# CorruptCore.net
KiCad netlist of a schematic drawn in EAGLE
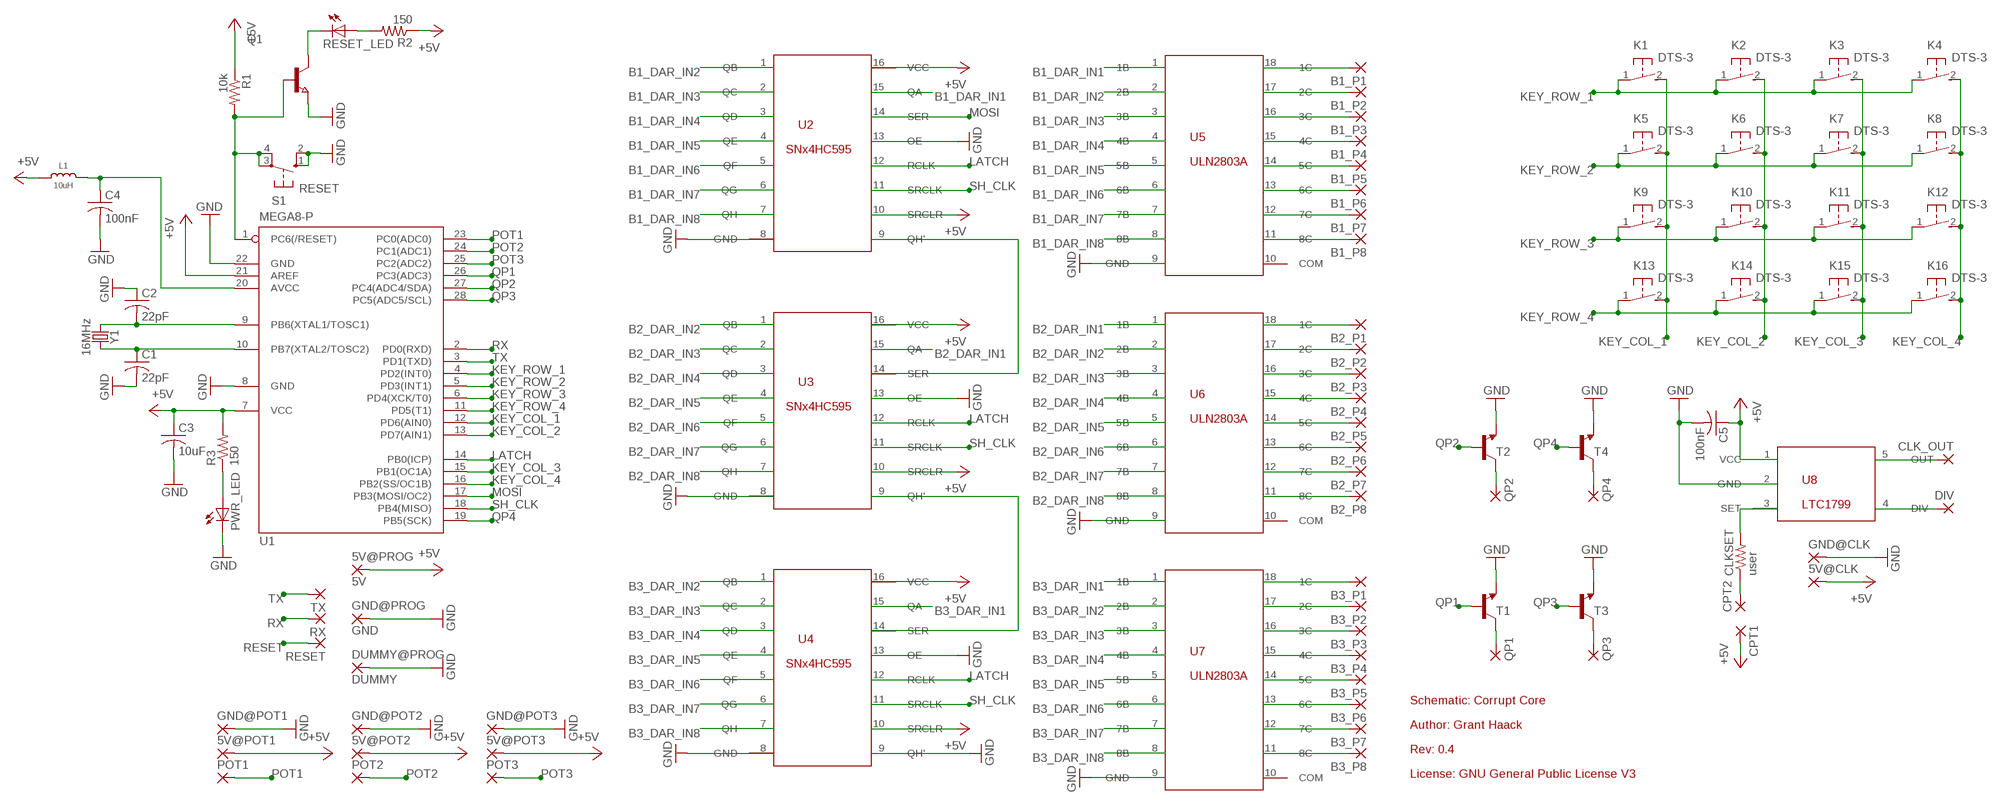
[diagram p0: schematic, sheet 1]

(export (version "E")
  (design (tool "Eeschema 10.0.6"))
  (components
    (comp (ref "5V@CLK")
      (value "1,6/0,8")
      (footprint "eagle-import:1,6_0,8")
      (libsource (lib "eagle-import") (part "1,6/0,8"))
    )
    (comp (ref "5V@POT1")
      (value "1,6/0,8")
      (footprint "eagle-import:1,6_0,8")
      (libsource (lib "eagle-import") (part "1,6/0,8"))
    )
    (comp (ref "5V@POT2")
      (value "1,6/0,8")
      (footprint "eagle-import:1,6_0,8")
      (libsource (lib "eagle-import") (part "1,6/0,8"))
    )
    (comp (ref "5V@POT3")
      (value "1,6/0,8")
      (footprint "eagle-import:1,6_0,8")
      (libsource (lib "eagle-import") (part "1,6/0,8"))
    )
    (comp (ref "5V@PROG")
      (value "5V")
      (footprint "eagle-import:1,6_0,8")
      (libsource (lib "eagle-import") (part "1,6/0,8"))
    )
    (comp (ref "B1_P1")
      (value "1,6/0,8")
      (footprint "eagle-import:1,6_0,8")
      (libsource (lib "eagle-import") (part "1,6/0,8"))
    )
    (comp (ref "B1_P2")
      (value "1,6/0,8")
      (footprint "eagle-import:1,6_0,8")
      (libsource (lib "eagle-import") (part "1,6/0,8"))
    )
    (comp (ref "B1_P3")
      (value "1,6/0,8")
      (footprint "eagle-import:1,6_0,8")
      (libsource (lib "eagle-import") (part "1,6/0,8"))
    )
    (comp (ref "B1_P4")
      (value "1,6/0,8")
      (footprint "eagle-import:1,6_0,8")
      (libsource (lib "eagle-import") (part "1,6/0,8"))
    )
    (comp (ref "B1_P5")
      (value "1,6/0,8")
      (footprint "eagle-import:1,6_0,8")
      (libsource (lib "eagle-import") (part "1,6/0,8"))
    )
    (comp (ref "B1_P6")
      (value "1,6/0,8")
      (footprint "eagle-import:1,6_0,8")
      (libsource (lib "eagle-import") (part "1,6/0,8"))
    )
    (comp (ref "B1_P7")
      (value "1,6/0,8")
      (footprint "eagle-import:1,6_0,8")
      (libsource (lib "eagle-import") (part "1,6/0,8"))
    )
    (comp (ref "B1_P8")
      (value "1,6/0,8")
      (footprint "eagle-import:1,6_0,8")
      (libsource (lib "eagle-import") (part "1,6/0,8"))
    )
    (comp (ref "B2_P1")
      (value "1,6/0,8")
      (footprint "eagle-import:1,6_0,8")
      (libsource (lib "eagle-import") (part "1,6/0,8"))
    )
    (comp (ref "B2_P2")
      (value "1,6/0,8")
      (footprint "eagle-import:1,6_0,8")
      (libsource (lib "eagle-import") (part "1,6/0,8"))
    )
    (comp (ref "B2_P3")
      (value "1,6/0,8")
      (footprint "eagle-import:1,6_0,8")
      (libsource (lib "eagle-import") (part "1,6/0,8"))
    )
    (comp (ref "B2_P4")
      (value "1,6/0,8")
      (footprint "eagle-import:1,6_0,8")
      (libsource (lib "eagle-import") (part "1,6/0,8"))
    )
    (comp (ref "B2_P5")
      (value "1,6/0,8")
      (footprint "eagle-import:1,6_0,8")
      (libsource (lib "eagle-import") (part "1,6/0,8"))
    )
    (comp (ref "B2_P6")
      (value "1,6/0,8")
      (footprint "eagle-import:1,6_0,8")
      (libsource (lib "eagle-import") (part "1,6/0,8"))
    )
    (comp (ref "B2_P7")
      (value "1,6/0,8")
      (footprint "eagle-import:1,6_0,8")
      (libsource (lib "eagle-import") (part "1,6/0,8"))
    )
    (comp (ref "B2_P8")
      (value "1,6/0,8")
      (footprint "eagle-import:1,6_0,8")
      (libsource (lib "eagle-import") (part "1,6/0,8"))
    )
    (comp (ref "B3_P1")
      (value "1,6/0,8")
      (footprint "eagle-import:1,6_0,8")
      (libsource (lib "eagle-import") (part "1,6/0,8"))
    )
    (comp (ref "B3_P2")
      (value "1,6/0,8")
      (footprint "eagle-import:1,6_0,8")
      (libsource (lib "eagle-import") (part "1,6/0,8"))
    )
    (comp (ref "B3_P3")
      (value "1,6/0,8")
      (footprint "eagle-import:1,6_0,8")
      (libsource (lib "eagle-import") (part "1,6/0,8"))
    )
    (comp (ref "B3_P4")
      (value "1,6/0,8")
      (footprint "eagle-import:1,6_0,8")
      (libsource (lib "eagle-import") (part "1,6/0,8"))
    )
    (comp (ref "B3_P5")
      (value "1,6/0,8")
      (footprint "eagle-import:1,6_0,8")
      (libsource (lib "eagle-import") (part "1,6/0,8"))
    )
    (comp (ref "B3_P6")
      (value "1,6/0,8")
      (footprint "eagle-import:1,6_0,8")
      (libsource (lib "eagle-import") (part "1,6/0,8"))
    )
    (comp (ref "B3_P7")
      (value "1,6/0,8")
      (footprint "eagle-import:1,6_0,8")
      (libsource (lib "eagle-import") (part "1,6/0,8"))
    )
    (comp (ref "B3_P8")
      (value "1,6/0,8")
      (footprint "eagle-import:1,6_0,8")
      (libsource (lib "eagle-import") (part "1,6/0,8"))
    )
    (comp (ref "C1")
      (value "22pF")
      (footprint "eagle-import:C0805")
      (libsource (lib "eagle-import") (part "C-USC0805"))
    )
    (comp (ref "C2")
      (value "22pF")
      (footprint "eagle-import:C0805")
      (libsource (lib "eagle-import") (part "C-USC0805"))
    )
    (comp (ref "C3")
      (value "10uF")
      (footprint "eagle-import:C0805")
      (libsource (lib "eagle-import") (part "C-USC0805"))
    )
    (comp (ref "C4")
      (value "100nF")
      (footprint "eagle-import:C0805")
      (libsource (lib "eagle-import") (part "C-USC0805"))
    )
    (comp (ref "C5")
      (value "100nF")
      (footprint "eagle-import:C0805")
      (libsource (lib "eagle-import") (part "C-USC0805"))
    )
    (comp (ref "CLKSET")
      (value "user")
      (footprint "eagle-import:0207_7")
      (libsource (lib "eagle-import") (part "R-US_0207/7"))
    )
    (comp (ref "CLK_OUT")
      (value "1,6/0,8")
      (footprint "eagle-import:1,6_0,8")
      (libsource (lib "eagle-import") (part "1,6/0,8"))
    )
    (comp (ref "CPT1")
      (value "1,6/0,8")
      (footprint "eagle-import:1,6_0,8")
      (libsource (lib "eagle-import") (part "1,6/0,8"))
    )
    (comp (ref "CPT2")
      (value "1,6/0,8")
      (footprint "eagle-import:1,6_0,8")
      (libsource (lib "eagle-import") (part "1,6/0,8"))
    )
    (comp (ref "DIV")
      (value "1,6/0,8")
      (footprint "eagle-import:1,6_0,8")
      (libsource (lib "eagle-import") (part "1,6/0,8"))
    )
    (comp (ref "DUMMY@PROG")
      (value "DUMMY")
      (footprint "eagle-import:1,6_0,8")
      (libsource (lib "eagle-import") (part "1,6/0,8"))
    )
    (comp (ref "GND@CLK")
      (value "1,6/0,8")
      (footprint "eagle-import:1,6_0,8")
      (libsource (lib "eagle-import") (part "1,6/0,8"))
    )
    (comp (ref "GND@POT1")
      (value "1,6/0,8")
      (footprint "eagle-import:1,6_0,8")
      (libsource (lib "eagle-import") (part "1,6/0,8"))
    )
    (comp (ref "GND@POT2")
      (value "1,6/0,8")
      (footprint "eagle-import:1,6_0,8")
      (libsource (lib "eagle-import") (part "1,6/0,8"))
    )
    (comp (ref "GND@POT3")
      (value "1,6/0,8")
      (footprint "eagle-import:1,6_0,8")
      (libsource (lib "eagle-import") (part "1,6/0,8"))
    )
    (comp (ref "GND@PROG")
      (value "GND")
      (footprint "eagle-import:1,6_0,8")
      (libsource (lib "eagle-import") (part "1,6/0,8"))
    )
    (comp (ref "K1")
      (value "DTS-3")
      (footprint "eagle-import:DTS-3")
      (libsource (lib "eagle-import") (part "DTS-3"))
    )
    (comp (ref "K2")
      (value "DTS-3")
      (footprint "eagle-import:DTS-3")
      (libsource (lib "eagle-import") (part "DTS-3"))
    )
    (comp (ref "K3")
      (value "DTS-3")
      (footprint "eagle-import:DTS-3")
      (libsource (lib "eagle-import") (part "DTS-3"))
    )
    (comp (ref "K4")
      (value "DTS-3")
      (footprint "eagle-import:DTS-3")
      (libsource (lib "eagle-import") (part "DTS-3"))
    )
    (comp (ref "K5")
      (value "DTS-3")
      (footprint "eagle-import:DTS-3")
      (libsource (lib "eagle-import") (part "DTS-3"))
    )
    (comp (ref "K6")
      (value "DTS-3")
      (footprint "eagle-import:DTS-3")
      (libsource (lib "eagle-import") (part "DTS-3"))
    )
    (comp (ref "K7")
      (value "DTS-3")
      (footprint "eagle-import:DTS-3")
      (libsource (lib "eagle-import") (part "DTS-3"))
    )
    (comp (ref "K8")
      (value "DTS-3")
      (footprint "eagle-import:DTS-3")
      (libsource (lib "eagle-import") (part "DTS-3"))
    )
    (comp (ref "K9")
      (value "DTS-3")
      (footprint "eagle-import:DTS-3")
      (libsource (lib "eagle-import") (part "DTS-3"))
    )
    (comp (ref "K10")
      (value "DTS-3")
      (footprint "eagle-import:DTS-3")
      (libsource (lib "eagle-import") (part "DTS-3"))
    )
    (comp (ref "K11")
      (value "DTS-3")
      (footprint "eagle-import:DTS-3")
      (libsource (lib "eagle-import") (part "DTS-3"))
    )
    (comp (ref "K12")
      (value "DTS-3")
      (footprint "eagle-import:DTS-3")
      (libsource (lib "eagle-import") (part "DTS-3"))
    )
    (comp (ref "K13")
      (value "DTS-3")
      (footprint "eagle-import:DTS-3")
      (libsource (lib "eagle-import") (part "DTS-3"))
    )
    (comp (ref "K14")
      (value "DTS-3")
      (footprint "eagle-import:DTS-3")
      (libsource (lib "eagle-import") (part "DTS-3"))
    )
    (comp (ref "K15")
      (value "DTS-3")
      (footprint "eagle-import:DTS-3")
      (libsource (lib "eagle-import") (part "DTS-3"))
    )
    (comp (ref "K16")
      (value "DTS-3")
      (footprint "eagle-import:DTS-3")
      (libsource (lib "eagle-import") (part "DTS-3"))
    )
    (comp (ref "L1")
      (value "10uH")
      (footprint "eagle-import:MICROBUILDER__0805")
      (libsource (lib "eagle-import") (part "MICROBUILDER_INDUCTOR_0805"))
    )
    (comp (ref "POT1")
      (value "1,6/0,8")
      (footprint "eagle-import:1,6_0,8")
      (libsource (lib "eagle-import") (part "1,6/0,8"))
    )
    (comp (ref "POT2")
      (value "1,6/0,8")
      (footprint "eagle-import:1,6_0,8")
      (libsource (lib "eagle-import") (part "1,6/0,8"))
    )
    (comp (ref "POT3")
      (value "1,6/0,8")
      (footprint "eagle-import:1,6_0,8")
      (libsource (lib "eagle-import") (part "1,6/0,8"))
    )
    (comp (ref "PWR_LED")
      (value "LEDCHIPLED_0603")
      (footprint "eagle-import:CHIPLED_0603")
      (libsource (lib "eagle-import") (part "LEDCHIPLED_0603"))
    )
    (comp (ref "Q1")
      (value "NPN-TRANSISTOR_SOT23")
      (footprint "eagle-import:SOT23")
      (libsource (lib "eagle-import") (part "NPN-TRANSISTOR_SOT23"))
    )
    (comp (ref "QP1")
      (value "1,6/0,8")
      (footprint "eagle-import:1,6_0,8")
      (libsource (lib "eagle-import") (part "1,6/0,8"))
    )
    (comp (ref "QP2")
      (value "1,6/0,8")
      (footprint "eagle-import:1,6_0,8")
      (libsource (lib "eagle-import") (part "1,6/0,8"))
    )
    (comp (ref "QP3")
      (value "1,6/0,8")
      (footprint "eagle-import:1,6_0,8")
      (libsource (lib "eagle-import") (part "1,6/0,8"))
    )
    (comp (ref "QP4")
      (value "1,6/0,8")
      (footprint "eagle-import:1,6_0,8")
      (libsource (lib "eagle-import") (part "1,6/0,8"))
    )
    (comp (ref "R1")
      (value "10k")
      (footprint "eagle-import:R0805")
      (libsource (lib "eagle-import") (part "R-US_R0805"))
    )
    (comp (ref "R2")
      (value "150")
      (footprint "eagle-import:R0805")
      (libsource (lib "eagle-import") (part "R-US_R0805"))
    )
    (comp (ref "R3")
      (value "150")
      (footprint "eagle-import:R0805")
      (libsource (lib "eagle-import") (part "R-US_R0805"))
    )
    (comp (ref "RESET")
      (value "1,6/0,8")
      (footprint "eagle-import:1,6_0,8")
      (libsource (lib "eagle-import") (part "1,6/0,8"))
    )
    (comp (ref "RESET_LED")
      (value "LEDCHIPLED_0603")
      (footprint "eagle-import:CHIPLED_0603")
      (libsource (lib "eagle-import") (part "LEDCHIPLED_0603"))
    )
    (comp (ref "RX")
      (value "1,6/0,8")
      (footprint "eagle-import:1,6_0,8")
      (libsource (lib "eagle-import") (part "1,6/0,8"))
    )
    (comp (ref "S1")
      (value "RESET")
      (footprint "eagle-import:B3F-10XX")
      (fields (field (name "MPN") "B3F-1000"))
      (libsource (lib "eagle-import") (part "10-XX"))
    )
    (comp (ref "T1")
      (value "TRANS_NPN-MMBTA42")
      (footprint "eagle-import:SOT23-3")
      (libsource (lib "eagle-import") (part "TRANS_NPN-MMBTA42"))
    )
    (comp (ref "T2")
      (value "TRANS_NPN-MMBTA42")
      (footprint "eagle-import:SOT23-3")
      (libsource (lib "eagle-import") (part "TRANS_NPN-MMBTA42"))
    )
    (comp (ref "T3")
      (value "TRANS_NPN-MMBTA42")
      (footprint "eagle-import:SOT23-3")
      (libsource (lib "eagle-import") (part "TRANS_NPN-MMBTA42"))
    )
    (comp (ref "T4")
      (value "TRANS_NPN-MMBTA42")
      (footprint "eagle-import:SOT23-3")
      (libsource (lib "eagle-import") (part "TRANS_NPN-MMBTA42"))
    )
    (comp (ref "TX")
      (value "1,6/0,8")
      (footprint "eagle-import:1,6_0,8")
      (libsource (lib "eagle-import") (part "1,6/0,8"))
    )
    (comp (ref "U1")
      (value "MEGA8-P")
      (footprint "eagle-import:DIL28-3")
      (libsource (lib "eagle-import") (part "MEGA8-P"))
    )
    (comp (ref "U2")
      (value "SNX4HC595SOIC16")
      (footprint "eagle-import:SOIC16N")
      (libsource (lib "eagle-import") (part "SNX4HC595SOIC16"))
    )
    (comp (ref "U3")
      (value "SNX4HC595SOIC16")
      (footprint "eagle-import:SOIC16N")
      (libsource (lib "eagle-import") (part "SNX4HC595SOIC16"))
    )
    (comp (ref "U4")
      (value "SNX4HC595SOIC16")
      (footprint "eagle-import:SOIC16N")
      (libsource (lib "eagle-import") (part "SNX4HC595SOIC16"))
    )
    (comp (ref "U5")
      (value "ULN2803ASOIC18")
      (footprint "eagle-import:SO18L")
      (libsource (lib "eagle-import") (part "ULN2803ASOIC18"))
    )
    (comp (ref "U6")
      (value "ULN2803ASOIC18")
      (footprint "eagle-import:SO18L")
      (libsource (lib "eagle-import") (part "ULN2803ASOIC18"))
    )
    (comp (ref "U7")
      (value "ULN2803ASOIC18")
      (footprint "eagle-import:SO18L")
      (libsource (lib "eagle-import") (part "ULN2803ASOIC18"))
    )
    (comp (ref "U8")
      (value "LTC1799")
      (footprint "eagle-import:SOT23-5L")
      (libsource (lib "eagle-import") (part "LTC1799"))
    )
    (comp (ref "Y1")
      (value "16MHz")
      (footprint "eagle-import:HC49US")
      (libsource (lib "eagle-import") (part "CRYSTAL-16MHZPTH-HC49US"))
    )
  )
  (nets
    (net (code "1") (name "+5V") (class "Default")
      (node (ref "5V@CLK") (pin "1") (pinfunction "P_1") (pintype "passive"))
      (node (ref "5V@POT1") (pin "1") (pinfunction "P_1") (pintype "passive"))
      (node (ref "5V@POT2") (pin "1") (pinfunction "P_1") (pintype "passive"))
      (node (ref "5V@POT3") (pin "1") (pinfunction "P_1") (pintype "passive"))
      (node (ref "5V@PROG") (pin "1") (pinfunction "P_1") (pintype "passive"))
      (node (ref "C3") (pin "1") (pinfunction "1_1") (pintype "passive"))
      (node (ref "C5") (pin "1") (pinfunction "1_1") (pintype "passive"))
      (node (ref "CPT1") (pin "1") (pinfunction "P_1") (pintype "passive"))
      (node (ref "L1") (pin "1") (pinfunction "1_1") (pintype "passive"))
      (node (ref "R1") (pin "1") (pinfunction "1_1") (pintype "passive"))
      (node (ref "R2") (pin "1") (pinfunction "1_1") (pintype "passive"))
      (node (ref "R3") (pin "2") (pinfunction "2_2") (pintype "passive"))
      (node (ref "U1") (pin "21") (pinfunction "AREF_21") (pintype "passive"))
      (node (ref "U1") (pin "7") (pinfunction "VCC_7") (pintype "power_in"))
      (node (ref "U2") (pin "10") (pinfunction "SRCLR_10") (pintype "bidirectional"))
      (node (ref "U2") (pin "16") (pinfunction "VCC_16") (pintype "bidirectional"))
      (node (ref "U3") (pin "10") (pinfunction "SRCLR_10") (pintype "bidirectional"))
      (node (ref "U3") (pin "16") (pinfunction "VCC_16") (pintype "bidirectional"))
      (node (ref "U4") (pin "10") (pinfunction "SRCLR_10") (pintype "bidirectional"))
      (node (ref "U4") (pin "16") (pinfunction "VCC_16") (pintype "bidirectional"))
      (node (ref "U8") (pin "1") (pinfunction "VCC_1") (pintype "bidirectional"))
    )
    (net (code "2") (name "/B1_DAR_IN1") (class "Default")
      (node (ref "U2") (pin "15") (pinfunction "QA_15") (pintype "bidirectional"))
      (node (ref "U5") (pin "1") (pinfunction "1B_1") (pintype "bidirectional"))
    )
    (net (code "3") (name "/B1_DAR_IN2") (class "Default")
      (node (ref "U2") (pin "1") (pinfunction "QB_1") (pintype "bidirectional"))
      (node (ref "U5") (pin "2") (pinfunction "2B_2") (pintype "bidirectional"))
    )
    (net (code "4") (name "/B1_DAR_IN3") (class "Default")
      (node (ref "U2") (pin "2") (pinfunction "QC_2") (pintype "bidirectional"))
      (node (ref "U5") (pin "3") (pinfunction "3B_3") (pintype "bidirectional"))
    )
    (net (code "5") (name "/B1_DAR_IN4") (class "Default")
      (node (ref "U2") (pin "3") (pinfunction "QD_3") (pintype "bidirectional"))
      (node (ref "U5") (pin "4") (pinfunction "4B_4") (pintype "bidirectional"))
    )
    (net (code "6") (name "/B1_DAR_IN5") (class "Default")
      (node (ref "U2") (pin "4") (pinfunction "QE_4") (pintype "bidirectional"))
      (node (ref "U5") (pin "5") (pinfunction "5B_5") (pintype "bidirectional"))
    )
    (net (code "7") (name "/B1_DAR_IN6") (class "Default")
      (node (ref "U2") (pin "5") (pinfunction "QF_5") (pintype "bidirectional"))
      (node (ref "U5") (pin "6") (pinfunction "6B_6") (pintype "bidirectional"))
    )
    (net (code "8") (name "/B1_DAR_IN7") (class "Default")
      (node (ref "U2") (pin "6") (pinfunction "QG_6") (pintype "bidirectional"))
      (node (ref "U5") (pin "7") (pinfunction "7B_7") (pintype "bidirectional"))
    )
    (net (code "9") (name "/B1_DAR_IN8") (class "Default")
      (node (ref "U2") (pin "7") (pinfunction "QH_7") (pintype "bidirectional"))
      (node (ref "U5") (pin "8") (pinfunction "8B_8") (pintype "bidirectional"))
    )
    (net (code "10") (name "/B2_DAR_IN1") (class "Default")
      (node (ref "U3") (pin "15") (pinfunction "QA_15") (pintype "bidirectional"))
      (node (ref "U6") (pin "1") (pinfunction "1B_1") (pintype "bidirectional"))
    )
    (net (code "11") (name "/B2_DAR_IN2") (class "Default")
      (node (ref "U3") (pin "1") (pinfunction "QB_1") (pintype "bidirectional"))
      (node (ref "U6") (pin "2") (pinfunction "2B_2") (pintype "bidirectional"))
    )
    (net (code "12") (name "/B2_DAR_IN3") (class "Default")
      (node (ref "U3") (pin "2") (pinfunction "QC_2") (pintype "bidirectional"))
      (node (ref "U6") (pin "3") (pinfunction "3B_3") (pintype "bidirectional"))
    )
    (net (code "13") (name "/B2_DAR_IN4") (class "Default")
      (node (ref "U3") (pin "3") (pinfunction "QD_3") (pintype "bidirectional"))
      (node (ref "U6") (pin "4") (pinfunction "4B_4") (pintype "bidirectional"))
    )
    (net (code "14") (name "/B2_DAR_IN5") (class "Default")
      (node (ref "U3") (pin "4") (pinfunction "QE_4") (pintype "bidirectional"))
      (node (ref "U6") (pin "5") (pinfunction "5B_5") (pintype "bidirectional"))
    )
    (net (code "15") (name "/B2_DAR_IN6") (class "Default")
      (node (ref "U3") (pin "5") (pinfunction "QF_5") (pintype "bidirectional"))
      (node (ref "U6") (pin "6") (pinfunction "6B_6") (pintype "bidirectional"))
    )
    (net (code "16") (name "/B2_DAR_IN7") (class "Default")
      (node (ref "U3") (pin "6") (pinfunction "QG_6") (pintype "bidirectional"))
      (node (ref "U6") (pin "7") (pinfunction "7B_7") (pintype "bidirectional"))
    )
    (net (code "17") (name "/B2_DAR_IN8") (class "Default")
      (node (ref "U3") (pin "7") (pinfunction "QH_7") (pintype "bidirectional"))
      (node (ref "U6") (pin "8") (pinfunction "8B_8") (pintype "bidirectional"))
    )
    (net (code "18") (name "/B3_DAR_IN1") (class "Default")
      (node (ref "U4") (pin "15") (pinfunction "QA_15") (pintype "bidirectional"))
      (node (ref "U7") (pin "1") (pinfunction "1B_1") (pintype "bidirectional"))
    )
    (net (code "19") (name "/B3_DAR_IN2") (class "Default")
      (node (ref "U4") (pin "1") (pinfunction "QB_1") (pintype "bidirectional"))
      (node (ref "U7") (pin "2") (pinfunction "2B_2") (pintype "bidirectional"))
    )
    (net (code "20") (name "/B3_DAR_IN3") (class "Default")
      (node (ref "U4") (pin "2") (pinfunction "QC_2") (pintype "bidirectional"))
      (node (ref "U7") (pin "3") (pinfunction "3B_3") (pintype "bidirectional"))
    )
    (net (code "21") (name "/B3_DAR_IN4") (class "Default")
      (node (ref "U4") (pin "3") (pinfunction "QD_3") (pintype "bidirectional"))
      (node (ref "U7") (pin "4") (pinfunction "4B_4") (pintype "bidirectional"))
    )
    (net (code "22") (name "/B3_DAR_IN5") (class "Default")
      (node (ref "U4") (pin "4") (pinfunction "QE_4") (pintype "bidirectional"))
      (node (ref "U7") (pin "5") (pinfunction "5B_5") (pintype "bidirectional"))
    )
    (net (code "23") (name "/B3_DAR_IN6") (class "Default")
      (node (ref "U4") (pin "5") (pinfunction "QF_5") (pintype "bidirectional"))
      (node (ref "U7") (pin "6") (pinfunction "6B_6") (pintype "bidirectional"))
    )
    (net (code "24") (name "/B3_DAR_IN7") (class "Default")
      (node (ref "U4") (pin "6") (pinfunction "QG_6") (pintype "bidirectional"))
      (node (ref "U7") (pin "7") (pinfunction "7B_7") (pintype "bidirectional"))
    )
    (net (code "25") (name "/B3_DAR_IN8") (class "Default")
      (node (ref "U4") (pin "7") (pinfunction "QH_7") (pintype "bidirectional"))
      (node (ref "U7") (pin "8") (pinfunction "8B_8") (pintype "bidirectional"))
    )
    (net (code "26") (name "/KEY_COL_1") (class "Default")
      (node (ref "K1") (pin "2") (pinfunction "2_2") (pintype "passive"))
      (node (ref "K13") (pin "2") (pinfunction "2_2") (pintype "passive"))
      (node (ref "K5") (pin "2") (pinfunction "2_2") (pintype "passive"))
      (node (ref "K9") (pin "2") (pinfunction "2_2") (pintype "passive"))
      (node (ref "U1") (pin "12") (pinfunction "PD6(AIN0)_12") (pintype "bidirectional"))
    )
    (net (code "27") (name "/KEY_COL_2") (class "Default")
      (node (ref "K10") (pin "2") (pinfunction "2_2") (pintype "passive"))
      (node (ref "K14") (pin "2") (pinfunction "2_2") (pintype "passive"))
      (node (ref "K2") (pin "2") (pinfunction "2_2") (pintype "passive"))
      (node (ref "K6") (pin "2") (pinfunction "2_2") (pintype "passive"))
      (node (ref "U1") (pin "13") (pinfunction "PD7(AIN1)_13") (pintype "bidirectional"))
    )
    (net (code "28") (name "/KEY_COL_3") (class "Default")
      (node (ref "K11") (pin "2") (pinfunction "2_2") (pintype "passive"))
      (node (ref "K15") (pin "2") (pinfunction "2_2") (pintype "passive"))
      (node (ref "K3") (pin "2") (pinfunction "2_2") (pintype "passive"))
      (node (ref "K7") (pin "2") (pinfunction "2_2") (pintype "passive"))
      (node (ref "U1") (pin "15") (pinfunction "PB1(OC1A)_15") (pintype "bidirectional"))
    )
    (net (code "29") (name "/KEY_COL_4") (class "Default")
      (node (ref "K12") (pin "2") (pinfunction "2_2") (pintype "passive"))
      (node (ref "K16") (pin "2") (pinfunction "2_2") (pintype "passive"))
      (node (ref "K4") (pin "2") (pinfunction "2_2") (pintype "passive"))
      (node (ref "K8") (pin "2") (pinfunction "2_2") (pintype "passive"))
      (node (ref "U1") (pin "16") (pinfunction "PB2(SS/OC1B)_16") (pintype "bidirectional"))
    )
    (net (code "30") (name "/KEY_ROW_1") (class "Default")
      (node (ref "K1") (pin "1") (pinfunction "1_1") (pintype "passive"))
      (node (ref "K2") (pin "1") (pinfunction "1_1") (pintype "passive"))
      (node (ref "K3") (pin "1") (pinfunction "1_1") (pintype "passive"))
      (node (ref "K4") (pin "1") (pinfunction "1_1") (pintype "passive"))
      (node (ref "U1") (pin "4") (pinfunction "PD2(INT0)_4") (pintype "bidirectional"))
    )
    (net (code "31") (name "/KEY_ROW_2") (class "Default")
      (node (ref "K5") (pin "1") (pinfunction "1_1") (pintype "passive"))
      (node (ref "K6") (pin "1") (pinfunction "1_1") (pintype "passive"))
      (node (ref "K7") (pin "1") (pinfunction "1_1") (pintype "passive"))
      (node (ref "K8") (pin "1") (pinfunction "1_1") (pintype "passive"))
      (node (ref "U1") (pin "5") (pinfunction "PD3(INT1)_5") (pintype "bidirectional"))
    )
    (net (code "32") (name "/KEY_ROW_3") (class "Default")
      (node (ref "K10") (pin "1") (pinfunction "1_1") (pintype "passive"))
      (node (ref "K11") (pin "1") (pinfunction "1_1") (pintype "passive"))
      (node (ref "K12") (pin "1") (pinfunction "1_1") (pintype "passive"))
      (node (ref "K9") (pin "1") (pinfunction "1_1") (pintype "passive"))
      (node (ref "U1") (pin "6") (pinfunction "PD4(XCK/T0)_6") (pintype "bidirectional"))
    )
    (net (code "33") (name "/KEY_ROW_4") (class "Default")
      (node (ref "K13") (pin "1") (pinfunction "1_1") (pintype "passive"))
      (node (ref "K14") (pin "1") (pinfunction "1_1") (pintype "passive"))
      (node (ref "K15") (pin "1") (pinfunction "1_1") (pintype "passive"))
      (node (ref "K16") (pin "1") (pinfunction "1_1") (pintype "passive"))
      (node (ref "U1") (pin "11") (pinfunction "PD5(T1)_11") (pintype "bidirectional"))
    )
    (net (code "34") (name "/LATCH") (class "Default")
      (node (ref "U1") (pin "14") (pinfunction "PB0(ICP)_14") (pintype "bidirectional"))
      (node (ref "U2") (pin "12") (pinfunction "RCLK_12") (pintype "bidirectional"))
      (node (ref "U3") (pin "12") (pinfunction "RCLK_12") (pintype "bidirectional"))
      (node (ref "U4") (pin "12") (pinfunction "RCLK_12") (pintype "bidirectional"))
    )
    (net (code "35") (name "/MOSI") (class "Default")
      (node (ref "U1") (pin "17") (pinfunction "PB3(MOSI/OC2)_17") (pintype "bidirectional"))
      (node (ref "U2") (pin "14") (pinfunction "SER_14") (pintype "bidirectional"))
    )
    (net (code "36") (name "/POT1") (class "Default")
      (node (ref "POT1") (pin "1") (pinfunction "P_1") (pintype "passive"))
      (node (ref "U1") (pin "23") (pinfunction "PC0(ADC0)_23") (pintype "bidirectional"))
    )
    (net (code "37") (name "/POT2") (class "Default")
      (node (ref "POT2") (pin "1") (pinfunction "P_1") (pintype "passive"))
      (node (ref "U1") (pin "24") (pinfunction "PC1(ADC1)_24") (pintype "bidirectional"))
    )
    (net (code "38") (name "/POT3") (class "Default")
      (node (ref "POT3") (pin "1") (pinfunction "P_1") (pintype "passive"))
      (node (ref "U1") (pin "25") (pinfunction "PC2(ADC2)_25") (pintype "bidirectional"))
    )
    (net (code "39") (name "/QP1") (class "Default")
      (node (ref "T1") (pin "1") (pinfunction "B_1") (pintype "passive"))
      (node (ref "U1") (pin "26") (pinfunction "PC3(ADC3)_26") (pintype "bidirectional"))
    )
    (net (code "40") (name "/QP2") (class "Default")
      (node (ref "T2") (pin "1") (pinfunction "B_1") (pintype "passive"))
      (node (ref "U1") (pin "27") (pinfunction "PC4(ADC4/SDA)_27") (pintype "bidirectional"))
    )
    (net (code "41") (name "/QP3") (class "Default")
      (node (ref "T3") (pin "1") (pinfunction "B_1") (pintype "passive"))
      (node (ref "U1") (pin "28") (pinfunction "PC5(ADC5/SCL)_28") (pintype "bidirectional"))
    )
    (net (code "42") (name "/QP4") (class "Default")
      (node (ref "T4") (pin "1") (pinfunction "B_1") (pintype "passive"))
      (node (ref "U1") (pin "19") (pinfunction "PB5(SCK)_19") (pintype "bidirectional"))
    )
    (net (code "43") (name "/RESET") (class "Default")
      (node (ref "Q1") (pin "1") (pinfunction "B_1") (pintype "passive"))
      (node (ref "R1") (pin "2") (pinfunction "2_2") (pintype "passive"))
      (node (ref "RESET") (pin "1") (pinfunction "P_1") (pintype "passive"))
      (node (ref "S1") (pin "3") (pinfunction "P_3") (pintype "passive"))
      (node (ref "S1") (pin "4") (pinfunction "P1_4") (pintype "passive"))
      (node (ref "U1") (pin "1") (pinfunction "PC6(/RESET)_1") (pintype "bidirectional"))
    )
    (net (code "44") (name "/RX") (class "Default")
      (node (ref "RX") (pin "1") (pinfunction "P_1") (pintype "passive"))
      (node (ref "U1") (pin "2") (pinfunction "PD0(RXD)_2") (pintype "bidirectional"))
    )
    (net (code "45") (name "/SH_CLK") (class "Default")
      (node (ref "U1") (pin "18") (pinfunction "PB4(MISO)_18") (pintype "bidirectional"))
      (node (ref "U2") (pin "11") (pinfunction "SRCLK_11") (pintype "bidirectional"))
      (node (ref "U3") (pin "11") (pinfunction "SRCLK_11") (pintype "bidirectional"))
      (node (ref "U4") (pin "11") (pinfunction "SRCLK_11") (pintype "bidirectional"))
    )
    (net (code "46") (name "/TX") (class "Default")
      (node (ref "TX") (pin "1") (pinfunction "P_1") (pintype "passive"))
      (node (ref "U1") (pin "3") (pinfunction "PD1(TXD)_3") (pintype "bidirectional"))
    )
    (net (code "47") (name "GND") (class "Default")
      (node (ref "C1") (pin "2") (pinfunction "2_2") (pintype "passive"))
      (node (ref "C2") (pin "1") (pinfunction "1_1") (pintype "passive"))
      (node (ref "C3") (pin "2") (pinfunction "2_2") (pintype "passive"))
      (node (ref "C4") (pin "2") (pinfunction "2_2") (pintype "passive"))
      (node (ref "C5") (pin "2") (pinfunction "2_2") (pintype "passive"))
      (node (ref "DUMMY@PROG") (pin "1") (pinfunction "P_1") (pintype "passive"))
      (node (ref "GND@CLK") (pin "1") (pinfunction "P_1") (pintype "passive"))
      (node (ref "GND@POT1") (pin "1") (pinfunction "P_1") (pintype "passive"))
      (node (ref "GND@POT2") (pin "1") (pinfunction "P_1") (pintype "passive"))
      (node (ref "GND@POT3") (pin "1") (pinfunction "P_1") (pintype "passive"))
      (node (ref "GND@PROG") (pin "1") (pinfunction "P_1") (pintype "passive"))
      (node (ref "PWR_LED") (pin "C") (pinfunction "C_C") (pintype "passive"))
      (node (ref "Q1") (pin "2") (pinfunction "E_2") (pintype "passive"))
      (node (ref "S1") (pin "1") (pinfunction "S_1") (pintype "passive"))
      (node (ref "S1") (pin "2") (pinfunction "S1_2") (pintype "passive"))
      (node (ref "T1") (pin "2") (pinfunction "E_2") (pintype "passive"))
      (node (ref "T2") (pin "2") (pinfunction "E_2") (pintype "passive"))
      (node (ref "T3") (pin "2") (pinfunction "E_2") (pintype "passive"))
      (node (ref "T4") (pin "2") (pinfunction "E_2") (pintype "passive"))
      (node (ref "U1") (pin "22") (pinfunction "GND_22") (pintype "power_in"))
      (node (ref "U1") (pin "8") (pinfunction "GND_8") (pintype "power_in"))
      (node (ref "U2") (pin "13") (pinfunction "OE_13") (pintype "bidirectional"))
      (node (ref "U2") (pin "8") (pinfunction "GND_8") (pintype "bidirectional"))
      (node (ref "U3") (pin "13") (pinfunction "OE_13") (pintype "bidirectional"))
      (node (ref "U3") (pin "8") (pinfunction "GND_8") (pintype "bidirectional"))
      (node (ref "U4") (pin "13") (pinfunction "OE_13") (pintype "bidirectional"))
      (node (ref "U4") (pin "8") (pinfunction "GND_8") (pintype "bidirectional"))
      (node (ref "U4") (pin "9") (pinfunction "QH'_9") (pintype "bidirectional"))
      (node (ref "U5") (pin "9") (pinfunction "GND_9") (pintype "bidirectional"))
      (node (ref "U6") (pin "9") (pinfunction "GND_9") (pintype "bidirectional"))
      (node (ref "U7") (pin "9") (pinfunction "GND_9") (pintype "bidirectional"))
      (node (ref "U8") (pin "2") (pinfunction "GND_2") (pintype "bidirectional"))
    )
    (net (code "48") (name "Net-(B1_P1-P)") (class "Default")
      (node (ref "B1_P1") (pin "1") (pinfunction "P_1") (pintype "passive"))
      (node (ref "U5") (pin "18") (pinfunction "1C_18") (pintype "bidirectional"))
    )
    (net (code "49") (name "Net-(B1_P2-P)") (class "Default")
      (node (ref "B1_P2") (pin "1") (pinfunction "P_1") (pintype "passive"))
      (node (ref "U5") (pin "17") (pinfunction "2C_17") (pintype "bidirectional"))
    )
    (net (code "50") (name "Net-(B1_P3-P)") (class "Default")
      (node (ref "B1_P3") (pin "1") (pinfunction "P_1") (pintype "passive"))
      (node (ref "U5") (pin "16") (pinfunction "3C_16") (pintype "bidirectional"))
    )
    (net (code "51") (name "Net-(B1_P4-P)") (class "Default")
      (node (ref "B1_P4") (pin "1") (pinfunction "P_1") (pintype "passive"))
      (node (ref "U5") (pin "15") (pinfunction "4C_15") (pintype "bidirectional"))
    )
    (net (code "52") (name "Net-(B1_P5-P)") (class "Default")
      (node (ref "B1_P5") (pin "1") (pinfunction "P_1") (pintype "passive"))
      (node (ref "U5") (pin "14") (pinfunction "5C_14") (pintype "bidirectional"))
    )
    (net (code "53") (name "Net-(B1_P6-P)") (class "Default")
      (node (ref "B1_P6") (pin "1") (pinfunction "P_1") (pintype "passive"))
      (node (ref "U5") (pin "13") (pinfunction "6C_13") (pintype "bidirectional"))
    )
    (net (code "54") (name "Net-(B1_P7-P)") (class "Default")
      (node (ref "B1_P7") (pin "1") (pinfunction "P_1") (pintype "passive"))
      (node (ref "U5") (pin "12") (pinfunction "7C_12") (pintype "bidirectional"))
    )
    (net (code "55") (name "Net-(B1_P8-P)") (class "Default")
      (node (ref "B1_P8") (pin "1") (pinfunction "P_1") (pintype "passive"))
      (node (ref "U5") (pin "11") (pinfunction "8C_11") (pintype "bidirectional"))
    )
    (net (code "56") (name "Net-(B2_P1-P)") (class "Default")
      (node (ref "B2_P1") (pin "1") (pinfunction "P_1") (pintype "passive"))
      (node (ref "U6") (pin "18") (pinfunction "1C_18") (pintype "bidirectional"))
    )
    (net (code "57") (name "Net-(B2_P2-P)") (class "Default")
      (node (ref "B2_P2") (pin "1") (pinfunction "P_1") (pintype "passive"))
      (node (ref "U6") (pin "17") (pinfunction "2C_17") (pintype "bidirectional"))
    )
    (net (code "58") (name "Net-(B2_P3-P)") (class "Default")
      (node (ref "B2_P3") (pin "1") (pinfunction "P_1") (pintype "passive"))
      (node (ref "U6") (pin "16") (pinfunction "3C_16") (pintype "bidirectional"))
    )
    (net (code "59") (name "Net-(B2_P4-P)") (class "Default")
      (node (ref "B2_P4") (pin "1") (pinfunction "P_1") (pintype "passive"))
      (node (ref "U6") (pin "15") (pinfunction "4C_15") (pintype "bidirectional"))
    )
    (net (code "60") (name "Net-(B2_P5-P)") (class "Default")
      (node (ref "B2_P5") (pin "1") (pinfunction "P_1") (pintype "passive"))
      (node (ref "U6") (pin "14") (pinfunction "5C_14") (pintype "bidirectional"))
    )
    (net (code "61") (name "Net-(B2_P6-P)") (class "Default")
      (node (ref "B2_P6") (pin "1") (pinfunction "P_1") (pintype "passive"))
      (node (ref "U6") (pin "13") (pinfunction "6C_13") (pintype "bidirectional"))
    )
    (net (code "62") (name "Net-(B2_P7-P)") (class "Default")
      (node (ref "B2_P7") (pin "1") (pinfunction "P_1") (pintype "passive"))
      (node (ref "U6") (pin "12") (pinfunction "7C_12") (pintype "bidirectional"))
    )
    (net (code "63") (name "Net-(B2_P8-P)") (class "Default")
      (node (ref "B2_P8") (pin "1") (pinfunction "P_1") (pintype "passive"))
      (node (ref "U6") (pin "11") (pinfunction "8C_11") (pintype "bidirectional"))
    )
    (net (code "64") (name "Net-(B3_P1-P)") (class "Default")
      (node (ref "B3_P1") (pin "1") (pinfunction "P_1") (pintype "passive"))
      (node (ref "U7") (pin "18") (pinfunction "1C_18") (pintype "bidirectional"))
    )
    (net (code "65") (name "Net-(B3_P2-P)") (class "Default")
      (node (ref "B3_P2") (pin "1") (pinfunction "P_1") (pintype "passive"))
      (node (ref "U7") (pin "17") (pinfunction "2C_17") (pintype "bidirectional"))
    )
    (net (code "66") (name "Net-(B3_P3-P)") (class "Default")
      (node (ref "B3_P3") (pin "1") (pinfunction "P_1") (pintype "passive"))
      (node (ref "U7") (pin "16") (pinfunction "3C_16") (pintype "bidirectional"))
    )
    (net (code "67") (name "Net-(B3_P4-P)") (class "Default")
      (node (ref "B3_P4") (pin "1") (pinfunction "P_1") (pintype "passive"))
      (node (ref "U7") (pin "15") (pinfunction "4C_15") (pintype "bidirectional"))
    )
    (net (code "68") (name "Net-(B3_P5-P)") (class "Default")
      (node (ref "B3_P5") (pin "1") (pinfunction "P_1") (pintype "passive"))
      (node (ref "U7") (pin "14") (pinfunction "5C_14") (pintype "bidirectional"))
    )
    (net (code "69") (name "Net-(B3_P6-P)") (class "Default")
      (node (ref "B3_P6") (pin "1") (pinfunction "P_1") (pintype "passive"))
      (node (ref "U7") (pin "13") (pinfunction "6C_13") (pintype "bidirectional"))
    )
    (net (code "70") (name "Net-(B3_P7-P)") (class "Default")
      (node (ref "B3_P7") (pin "1") (pinfunction "P_1") (pintype "passive"))
      (node (ref "U7") (pin "12") (pinfunction "7C_12") (pintype "bidirectional"))
    )
    (net (code "71") (name "Net-(B3_P8-P)") (class "Default")
      (node (ref "B3_P8") (pin "1") (pinfunction "P_1") (pintype "passive"))
      (node (ref "U7") (pin "11") (pinfunction "8C_11") (pintype "bidirectional"))
    )
    (net (code "72") (name "Net-(CLK_OUT-P)") (class "Default")
      (node (ref "CLK_OUT") (pin "1") (pinfunction "P_1") (pintype "passive"))
      (node (ref "U8") (pin "5") (pinfunction "OUT_5") (pintype "bidirectional"))
    )
    (net (code "73") (name "Net-(CPT2-P)") (class "Default")
      (node (ref "CLKSET") (pin "1") (pinfunction "1_1") (pintype "passive"))
      (node (ref "CPT2") (pin "1") (pinfunction "P_1") (pintype "passive"))
    )
    (net (code "74") (name "Net-(DIV-P)") (class "Default")
      (node (ref "DIV") (pin "1") (pinfunction "P_1") (pintype "passive"))
      (node (ref "U8") (pin "4") (pinfunction "DIV_4") (pintype "bidirectional"))
    )
    (net (code "75") (name "Net-(PWR_LED-PadA)") (class "Default")
      (node (ref "PWR_LED") (pin "A") (pinfunction "A_A") (pintype "passive"))
      (node (ref "R3") (pin "1") (pinfunction "1_1") (pintype "passive"))
    )
    (net (code "76") (name "Net-(Q1-C)") (class "Default")
      (node (ref "Q1") (pin "3") (pinfunction "C_3") (pintype "passive"))
      (node (ref "RESET_LED") (pin "C") (pinfunction "C_C") (pintype "passive"))
    )
    (net (code "77") (name "Net-(QP1-P)") (class "Default")
      (node (ref "QP1") (pin "1") (pinfunction "P_1") (pintype "passive"))
      (node (ref "T1") (pin "3") (pinfunction "C_3") (pintype "passive"))
    )
    (net (code "78") (name "Net-(QP2-P)") (class "Default")
      (node (ref "QP2") (pin "1") (pinfunction "P_1") (pintype "passive"))
      (node (ref "T2") (pin "3") (pinfunction "C_3") (pintype "passive"))
    )
    (net (code "79") (name "Net-(QP3-P)") (class "Default")
      (node (ref "QP3") (pin "1") (pinfunction "P_1") (pintype "passive"))
      (node (ref "T3") (pin "3") (pinfunction "C_3") (pintype "passive"))
    )
    (net (code "80") (name "Net-(QP4-P)") (class "Default")
      (node (ref "QP4") (pin "1") (pinfunction "P_1") (pintype "passive"))
      (node (ref "T4") (pin "3") (pinfunction "C_3") (pintype "passive"))
    )
    (net (code "81") (name "Net-(R2-Pad2)") (class "Default")
      (node (ref "R2") (pin "2") (pinfunction "2_2") (pintype "passive"))
      (node (ref "RESET_LED") (pin "A") (pinfunction "A_A") (pintype "passive"))
    )
    (net (code "82") (name "Net-(U1-AVCC)") (class "Default")
      (node (ref "C4") (pin "1") (pinfunction "1_1") (pintype "passive"))
      (node (ref "L1") (pin "2") (pinfunction "2_2") (pintype "passive"))
      (node (ref "U1") (pin "20") (pinfunction "AVCC_20") (pintype "power_in"))
    )
    (net (code "83") (name "Net-(U1-PB6(XTAL1{slash}TOSC1))") (class "Default")
      (node (ref "C2") (pin "2") (pinfunction "2_2") (pintype "passive"))
      (node (ref "U1") (pin "9") (pinfunction "PB6(XTAL1/TOSC1)_9") (pintype "bidirectional"))
      (node (ref "Y1") (pin "1") (pinfunction "1_1") (pintype "passive"))
    )
    (net (code "84") (name "Net-(U1-PB7(XTAL2{slash}TOSC2))") (class "Default")
      (node (ref "C1") (pin "1") (pinfunction "1_1") (pintype "passive"))
      (node (ref "U1") (pin "10") (pinfunction "PB7(XTAL2/TOSC2)_10") (pintype "bidirectional"))
      (node (ref "Y1") (pin "2") (pinfunction "2_2") (pintype "passive"))
    )
    (net (code "85") (name "Net-(U2-QH')") (class "Default")
      (node (ref "U2") (pin "9") (pinfunction "QH'_9") (pintype "bidirectional"))
      (node (ref "U3") (pin "14") (pinfunction "SER_14") (pintype "bidirectional"))
    )
    (net (code "86") (name "Net-(U3-QH')") (class "Default")
      (node (ref "U3") (pin "9") (pinfunction "QH'_9") (pintype "bidirectional"))
      (node (ref "U4") (pin "14") (pinfunction "SER_14") (pintype "bidirectional"))
    )
    (net (code "87") (name "Net-(U8-SET)") (class "Default")
      (node (ref "CLKSET") (pin "2") (pinfunction "2_2") (pintype "passive"))
      (node (ref "U8") (pin "3") (pinfunction "SET_3") (pintype "bidirectional"))
    )
    (net (code "88") (name "unconnected-(U5-COM-Pad10)") (class "Default")
      (node (ref "U5") (pin "10") (pinfunction "COM_10") (pintype "bidirectional"))
    )
    (net (code "89") (name "unconnected-(U6-COM-Pad10)") (class "Default")
      (node (ref "U6") (pin "10") (pinfunction "COM_10") (pintype "bidirectional"))
    )
    (net (code "90") (name "unconnected-(U7-COM-Pad10)") (class "Default")
      (node (ref "U7") (pin "10") (pinfunction "COM_10") (pintype "bidirectional"))
    )
  )
)
